# coffee-bot.net
KiCad netlist of a schematic drawn in EAGLE
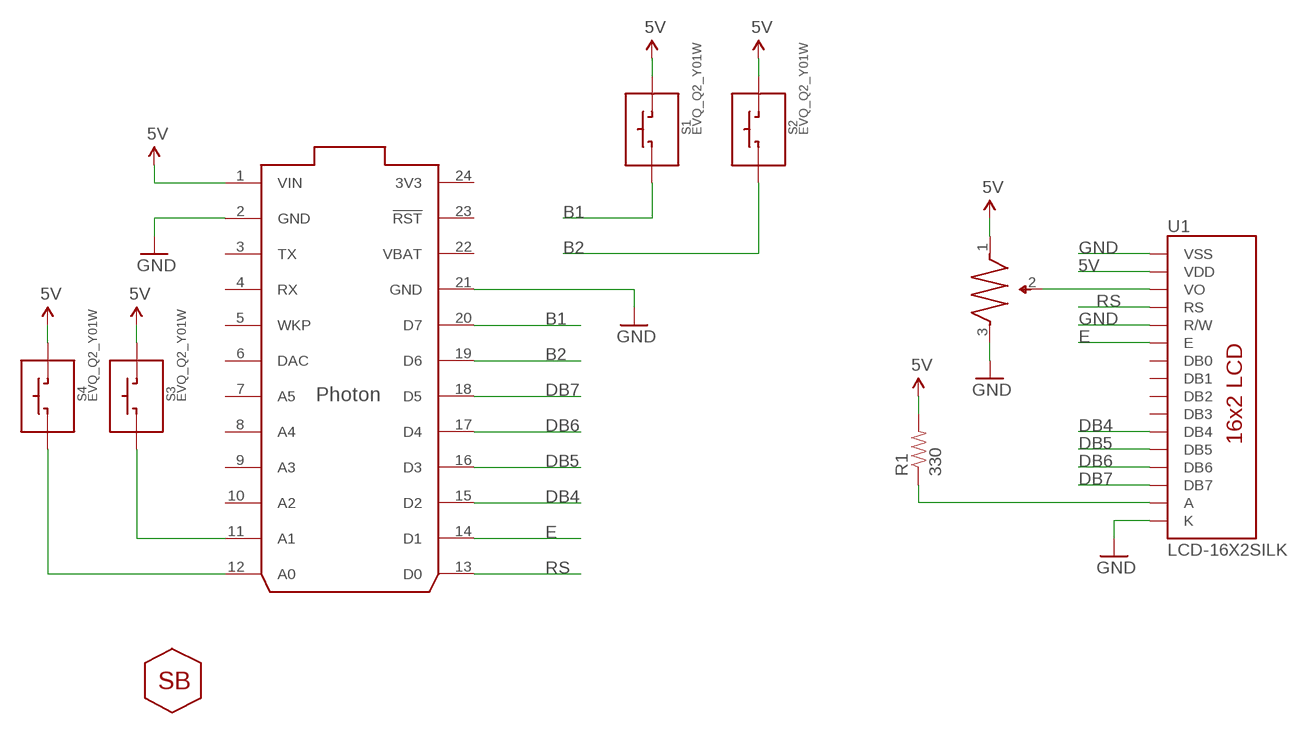
[diagram p0: schematic, sheet 1]

(export (version "E")
  (design (tool "Eeschema 10.0.6"))
  (components
    (comp (ref "R1")
      (value "330")
      (footprint "eagle-import:1206")
      (libsource (lib "eagle-import") (part "RESISTOR1206"))
    )
    (comp (ref "S1")
      (value "EVQ_Q2_Y01W")
      (footprint "eagle-import:EVQQ2")
      (libsource (lib "eagle-import") (part "EVQ_Q2_Y01W"))
    )
    (comp (ref "S2")
      (value "EVQ_Q2_Y01W")
      (footprint "eagle-import:EVQQ2")
      (libsource (lib "eagle-import") (part "EVQ_Q2_Y01W"))
    )
    (comp (ref "S3")
      (value "EVQ_Q2_Y01W")
      (footprint "eagle-import:EVQQ2")
      (libsource (lib "eagle-import") (part "EVQ_Q2_Y01W"))
    )
    (comp (ref "S4")
      (value "EVQ_Q2_Y01W")
      (footprint "eagle-import:EVQQ2")
      (libsource (lib "eagle-import") (part "EVQ_Q2_Y01W"))
    )
    (comp (ref "U$2")
      (value "TC-33X2")
      (footprint "eagle-import:TC-33X2")
      (libsource (lib "eagle-import") (part "TC-33X2"))
    )
    (comp (ref "U$3")
      (value "SBLOGO250MIL")
      (footprint "eagle-import:SBLOGO")
      (libsource (lib "eagle-import") (part "SBLOGO250MIL"))
    )
    (comp (ref "U1")
      (value "LCD-16X2SILK")
      (footprint "eagle-import:LCD-16X2")
      (libsource (lib "eagle-import") (part "LCD-16X2SILK"))
    )
    (comp (ref "U2")
      (value "PHOTON_SMD")
      (footprint "eagle-import:PHOTON_SMD")
      (libsource (lib "eagle-import") (part "PHOTON_SMD"))
    )
  )
  (nets
    (net (code "1") (name "/3V3") (class "Default")
      (node (ref "U2") (pin "24") (pinfunction "3V3_24") (pintype "power_in"))
    )
    (net (code "2") (name "/B1") (class "Default")
      (node (ref "S1") (pin "A1") (pinfunction "A_A1") (pintype "bidirectional"))
      (node (ref "S1") (pin "A2") (pinfunction "A_A2") (pintype "bidirectional"))
      (node (ref "U2") (pin "20") (pinfunction "D7_20") (pintype "bidirectional"))
    )
    (net (code "3") (name "/B2") (class "Default")
      (node (ref "S2") (pin "A1") (pinfunction "A_A1") (pintype "bidirectional"))
      (node (ref "S2") (pin "A2") (pinfunction "A_A2") (pintype "bidirectional"))
      (node (ref "U2") (pin "19") (pinfunction "D6_19") (pintype "bidirectional"))
    )
    (net (code "4") (name "/DB4") (class "Default")
      (node (ref "U1") (pin "11") (pinfunction "DB4_11") (pintype "bidirectional"))
      (node (ref "U2") (pin "15") (pinfunction "D2_15") (pintype "bidirectional"))
    )
    (net (code "5") (name "/DB5") (class "Default")
      (node (ref "U1") (pin "12") (pinfunction "DB5_12") (pintype "bidirectional"))
      (node (ref "U2") (pin "16") (pinfunction "D3_16") (pintype "bidirectional"))
    )
    (net (code "6") (name "/DB6") (class "Default")
      (node (ref "U1") (pin "13") (pinfunction "DB6_13") (pintype "bidirectional"))
      (node (ref "U2") (pin "17") (pinfunction "D4_17") (pintype "bidirectional"))
    )
    (net (code "7") (name "/DB7") (class "Default")
      (node (ref "U1") (pin "14") (pinfunction "DB7_14") (pintype "bidirectional"))
      (node (ref "U2") (pin "18") (pinfunction "D5_18") (pintype "bidirectional"))
    )
    (net (code "8") (name "/E") (class "Default")
      (node (ref "U1") (pin "6") (pinfunction "E_6") (pintype "input"))
      (node (ref "U2") (pin "14") (pinfunction "D1_14") (pintype "bidirectional"))
    )
    (net (code "9") (name "/RS") (class "Default")
      (node (ref "U1") (pin "4") (pinfunction "RS_4") (pintype "input"))
      (node (ref "U2") (pin "13") (pinfunction "D0_13") (pintype "bidirectional"))
    )
    (net (code "10") (name "/VBAT") (class "Default")
      (node (ref "U2") (pin "22") (pinfunction "VBAT_22") (pintype "power_in"))
    )
    (net (code "11") (name "5V") (class "Default")
      (node (ref "R1") (pin "2") (pinfunction "2_2") (pintype "passive"))
      (node (ref "S1") (pin "B1") (pinfunction "B_B1") (pintype "bidirectional"))
      (node (ref "S1") (pin "B2") (pinfunction "B_B2") (pintype "bidirectional"))
      (node (ref "S2") (pin "B1") (pinfunction "B_B1") (pintype "bidirectional"))
      (node (ref "S2") (pin "B2") (pinfunction "B_B2") (pintype "bidirectional"))
      (node (ref "S3") (pin "B1") (pinfunction "B_B1") (pintype "bidirectional"))
      (node (ref "S3") (pin "B2") (pinfunction "B_B2") (pintype "bidirectional"))
      (node (ref "S4") (pin "B1") (pinfunction "B_B1") (pintype "bidirectional"))
      (node (ref "S4") (pin "B2") (pinfunction "B_B2") (pintype "bidirectional"))
      (node (ref "U$2") (pin "1") (pinfunction "P$1_1") (pintype "bidirectional"))
      (node (ref "U1") (pin "2") (pinfunction "VDD_2") (pintype "power_in"))
      (node (ref "U2") (pin "1") (pinfunction "VIN_1") (pintype "power_in"))
    )
    (net (code "12") (name "GND") (class "Default")
      (node (ref "U$2") (pin "3") (pinfunction "P$3_3") (pintype "bidirectional"))
      (node (ref "U1") (pin "1") (pinfunction "VSS_1") (pintype "power_in"))
      (node (ref "U1") (pin "16") (pinfunction "K_16") (pintype "power_in"))
      (node (ref "U1") (pin "5") (pinfunction "R/W_5") (pintype "input"))
      (node (ref "U2") (pin "2") (pinfunction "GND_2") (pintype "power_in"))
      (node (ref "U2") (pin "21") (pinfunction "GND_21") (pintype "power_in"))
    )
    (net (code "13") (name "Net-(U$2-P$2)") (class "Default")
      (node (ref "U$2") (pin "2") (pinfunction "P$2_2") (pintype "bidirectional"))
      (node (ref "U1") (pin "3") (pinfunction "VO_3") (pintype "bidirectional"))
    )
    (net (code "14") (name "Net-(U1-A)") (class "Default")
      (node (ref "R1") (pin "1") (pinfunction "1_1") (pintype "passive"))
      (node (ref "U1") (pin "15") (pinfunction "A_15") (pintype "power_in"))
    )
    (net (code "15") (name "Net-(U2A-A0)") (class "Default")
      (node (ref "S4") (pin "A1") (pinfunction "A_A1") (pintype "bidirectional"))
      (node (ref "S4") (pin "A2") (pinfunction "A_A2") (pintype "bidirectional"))
      (node (ref "U2") (pin "12") (pinfunction "A0_12") (pintype "bidirectional"))
    )
    (net (code "16") (name "Net-(U2A-A1)") (class "Default")
      (node (ref "S3") (pin "A1") (pinfunction "A_A1") (pintype "bidirectional"))
      (node (ref "S3") (pin "A2") (pinfunction "A_A2") (pintype "bidirectional"))
      (node (ref "U2") (pin "11") (pinfunction "A1_11") (pintype "bidirectional"))
    )
    (net (code "17") (name "unconnected-(U1-DB0-Pad7)") (class "Default")
      (node (ref "U1") (pin "7") (pinfunction "DB0_7") (pintype "bidirectional"))
    )
    (net (code "18") (name "unconnected-(U1-DB1-Pad8)") (class "Default")
      (node (ref "U1") (pin "8") (pinfunction "DB1_8") (pintype "bidirectional"))
    )
    (net (code "19") (name "unconnected-(U1-DB2-Pad9)") (class "Default")
      (node (ref "U1") (pin "9") (pinfunction "DB2_9") (pintype "bidirectional"))
    )
    (net (code "20") (name "unconnected-(U1-DB3-Pad10)") (class "Default")
      (node (ref "U1") (pin "10") (pinfunction "DB3_10") (pintype "bidirectional"))
    )
    (net (code "21") (name "unconnected-(U2A-A2-Pad10)") (class "Default")
      (node (ref "U2") (pin "10") (pinfunction "A2_10") (pintype "bidirectional"))
    )
    (net (code "22") (name "unconnected-(U2A-A3-Pad9)") (class "Default")
      (node (ref "U2") (pin "9") (pinfunction "A3_9") (pintype "bidirectional"))
    )
    (net (code "23") (name "unconnected-(U2A-A4-Pad8)") (class "Default")
      (node (ref "U2") (pin "8") (pinfunction "A4_8") (pintype "bidirectional"))
    )
    (net (code "24") (name "unconnected-(U2A-A5-Pad7)") (class "Default")
      (node (ref "U2") (pin "7") (pinfunction "A5_7") (pintype "bidirectional"))
    )
    (net (code "25") (name "unconnected-(U2A-DAC-Pad6)") (class "Default")
      (node (ref "U2") (pin "6") (pinfunction "DAC_6") (pintype "bidirectional"))
    )
    (net (code "26") (name "unconnected-(U2A-RX-Pad4)") (class "Default")
      (node (ref "U2") (pin "4") (pinfunction "RX_4") (pintype "bidirectional"))
    )
    (net (code "27") (name "unconnected-(U2A-TX-Pad3)") (class "Default")
      (node (ref "U2") (pin "3") (pinfunction "TX_3") (pintype "bidirectional"))
    )
    (net (code "28") (name "unconnected-(U2A-WKP-Pad5)") (class "Default")
      (node (ref "U2") (pin "5") (pinfunction "WKP_5") (pintype "bidirectional"))
    )
    (net (code "29") (name "unconnected-(U2A-~{RST}-Pad23)") (class "Default")
      (node (ref "U2") (pin "23") (pinfunction "~{RST}_23") (pintype "bidirectional"))
    )
  )
)
